# sandbox_jack_2c.net
KiCad netlist of a schematic drawn in EAGLE
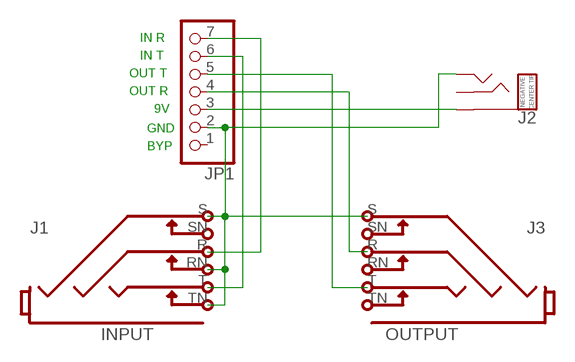
[diagram p0: schematic, sheet 1]

(export (version "E")
  (design (tool "Eeschema 10.0.6"))
  (components
    (comp (ref "J1")
      (value "STEREOSW3NOMOUNT")
      (footprint "eagle-import:NEUTRIK-NRJ6HF-NOMOUNT")
      (libsource (lib "eagle-import") (part "STEREOSW3NOMOUNT"))
    )
    (comp (ref "J2")
      (value "DC_TRS")
      (footprint "eagle-import:JACK_DC_PC-MOUNT_2.1MM_NO-KEEPOUT")
      (libsource (lib "eagle-import") (part "DC_TRS"))
    )
    (comp (ref "J3")
      (value "STEREOSW3NOMOUNT")
      (footprint "eagle-import:NEUTRIK-NRJ6HF-NOMOUNT")
      (libsource (lib "eagle-import") (part "STEREOSW3NOMOUNT"))
    )
    (comp (ref "JP1")
      (value "PINHD-1X7")
      (footprint "eagle-import:1X07")
      (libsource (lib "eagle-import") (part "PINHD-1X7"))
    )
  )
  (nets
    (net (code "1") (name "Net-(J1-PadR)") (class "Default")
      (node (ref "J1") (pin "R") (pinfunction "R_R") (pintype "passive"))
      (node (ref "JP1") (pin "7") (pinfunction "7_7") (pintype "passive"))
    )
    (net (code "2") (name "Net-(J1-PadT)") (class "Default")
      (node (ref "J1") (pin "T") (pinfunction "T_T") (pintype "passive"))
      (node (ref "JP1") (pin "6") (pinfunction "6_6") (pintype "passive"))
    )
    (net (code "3") (name "Net-(J2-GND)") (class "Default")
      (node (ref "J1") (pin "RN") (pinfunction "RN_RN") (pintype "passive"))
      (node (ref "J1") (pin "S") (pinfunction "S_S") (pintype "passive"))
      (node (ref "J1") (pin "TN") (pinfunction "TN_TN") (pintype "passive"))
      (node (ref "J2") (pin "3") (pinfunction "GND_3") (pintype "bidirectional"))
      (node (ref "J3") (pin "S") (pinfunction "S_S") (pintype "passive"))
      (node (ref "JP1") (pin "2") (pinfunction "2_2") (pintype "passive"))
    )
    (net (code "4") (name "Net-(J2-PWR)") (class "Default")
      (node (ref "J2") (pin "1") (pinfunction "PWR_1") (pintype "bidirectional"))
      (node (ref "JP1") (pin "3") (pinfunction "3_3") (pintype "passive"))
    )
    (net (code "5") (name "Net-(J3-PadR)") (class "Default")
      (node (ref "J3") (pin "R") (pinfunction "R_R") (pintype "passive"))
      (node (ref "JP1") (pin "4") (pinfunction "4_4") (pintype "passive"))
    )
    (net (code "6") (name "Net-(J3-PadT)") (class "Default")
      (node (ref "J3") (pin "T") (pinfunction "T_T") (pintype "passive"))
      (node (ref "JP1") (pin "5") (pinfunction "5_5") (pintype "passive"))
    )
    (net (code "7") (name "unconnected-(J1-PadSN)") (class "Default")
      (node (ref "J1") (pin "SN") (pinfunction "SN_SN") (pintype "passive"))
    )
    (net (code "8") (name "unconnected-(J2-RNG-Pad2)") (class "Default")
      (node (ref "J2") (pin "2") (pinfunction "RNG_2") (pintype "bidirectional"))
    )
    (net (code "9") (name "unconnected-(J3-PadRN)") (class "Default")
      (node (ref "J3") (pin "RN") (pinfunction "RN_RN") (pintype "passive"))
    )
    (net (code "10") (name "unconnected-(J3-PadSN)") (class "Default")
      (node (ref "J3") (pin "SN") (pinfunction "SN_SN") (pintype "passive"))
    )
    (net (code "11") (name "unconnected-(J3-PadTN)") (class "Default")
      (node (ref "J3") (pin "TN") (pinfunction "TN_TN") (pintype "passive"))
    )
    (net (code "12") (name "unconnected-(JP1-Pad1)") (class "Default")
      (node (ref "JP1") (pin "1") (pinfunction "1_1") (pintype "passive"))
    )
  )
)
